# P10_HDMI_Framer.net
KiCad netlist of a schematic drawn in Altium Designer
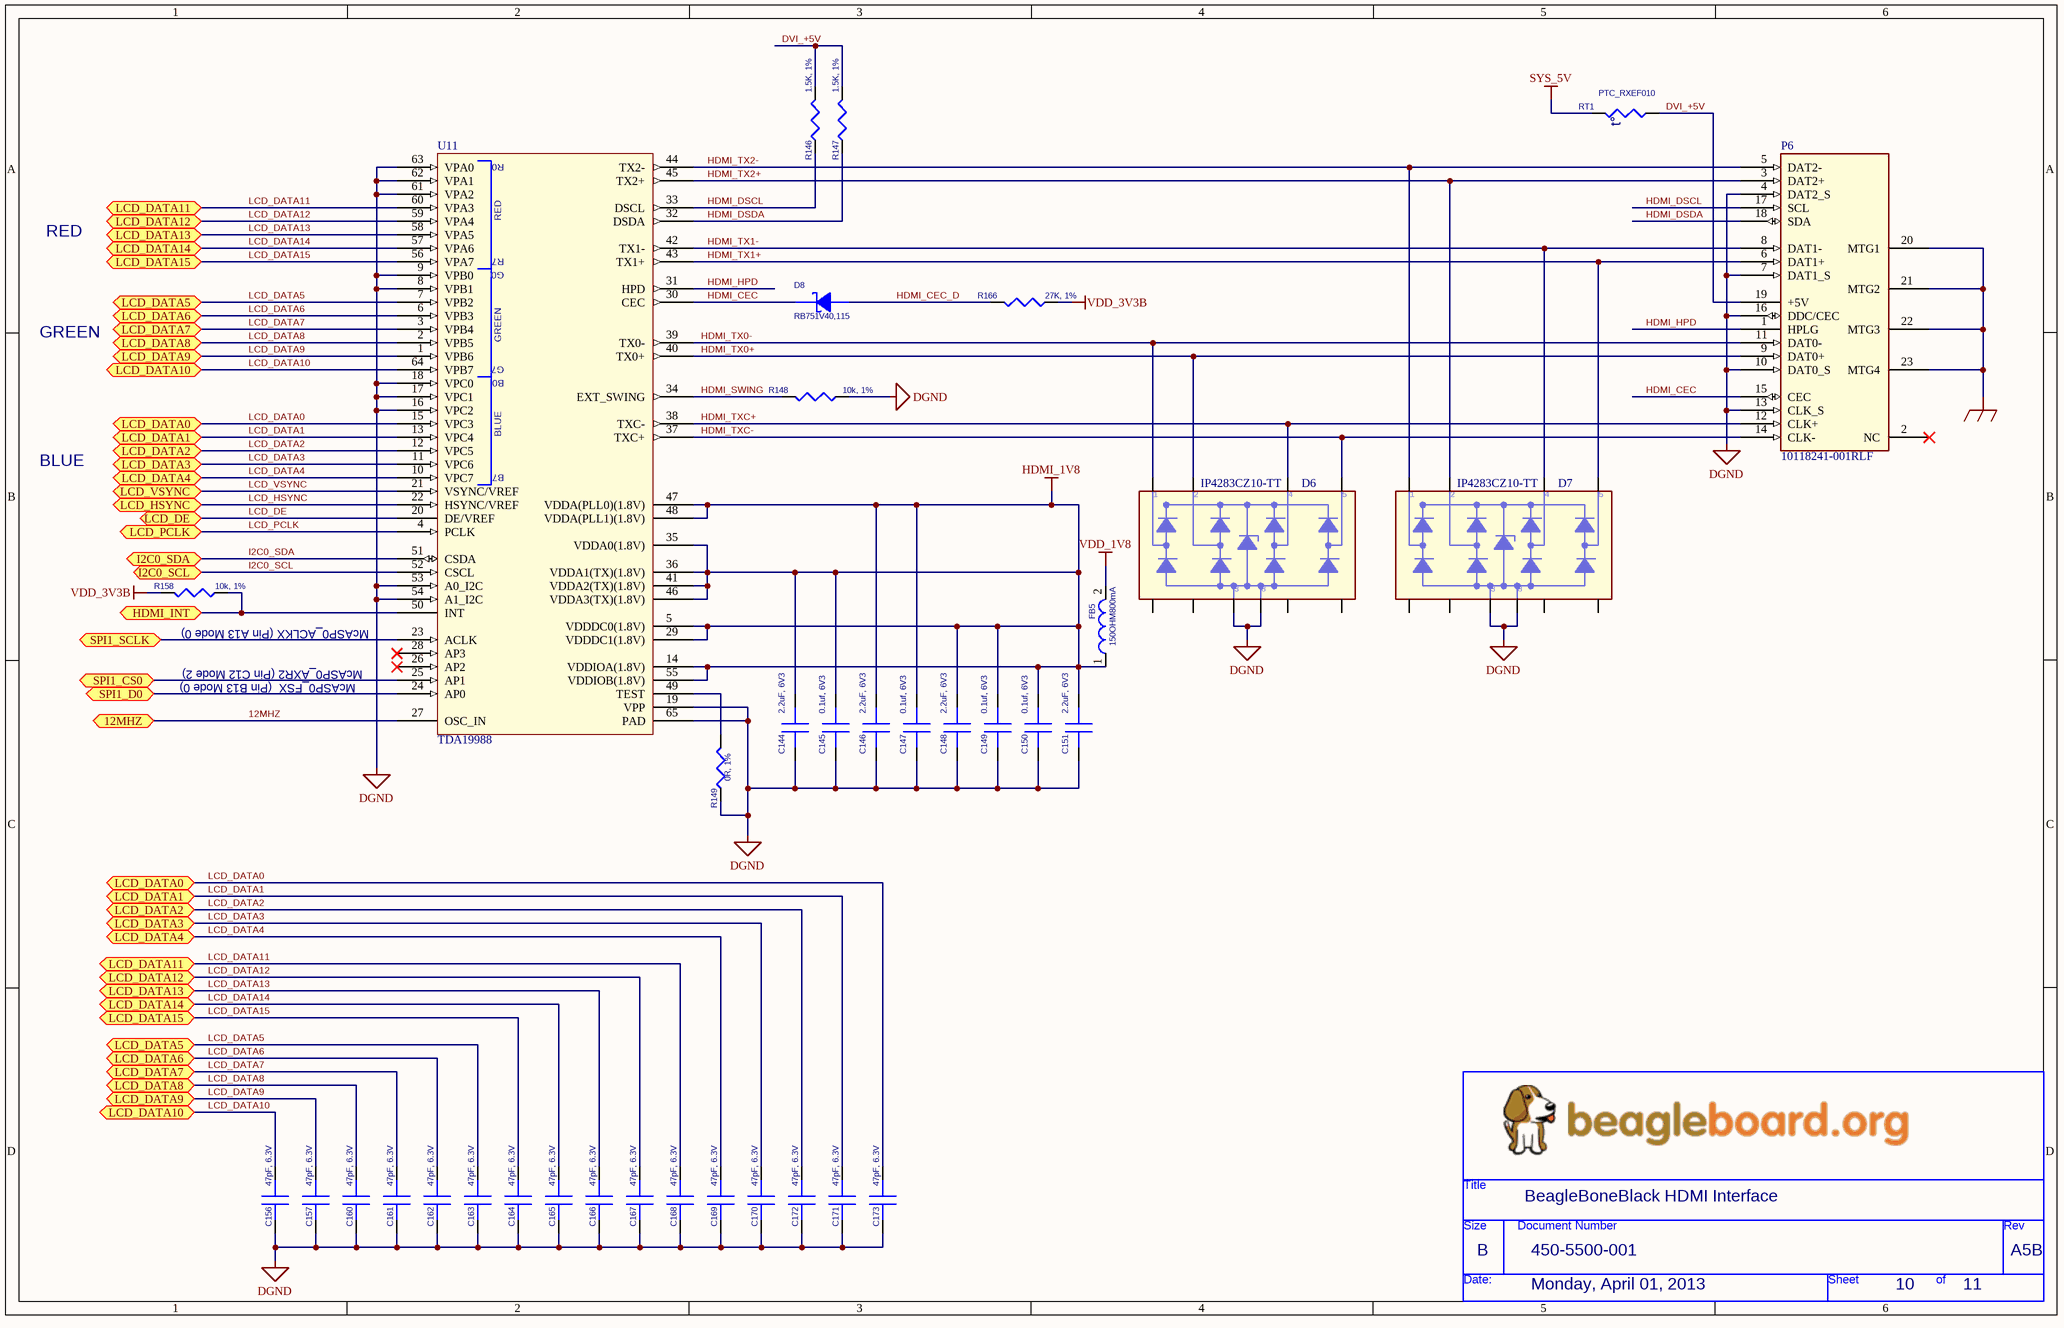
[diagram p0: P10_HDMI Framer.SchDoc]

(export (version "E")
  (design (tool "Eeschema 10.0.6"))
  (components
    (comp (ref "C144")
      (value "2.2uF, 6V3")
      (footprint "402")
      (description "CAP CER 2.2UF 6.3V 10% X5R 0402")
      (fields
        (field (name "MANUFACTURER") "TDK Corporation")
        (field (name "MANUFACTURER PART NUMBER") "C1005X5R0J225K050BC")
      )
      (libsource (lib "BEAGLEBONEBLACK_REV A5B") (part "CAP SMD"))
    )
    (comp (ref "C145")
      (value "0.1uf, 6V3")
      (footprint "402")
      (description "CAP CER 0.1UF 6.3V 10% X5R 0402")
      (fields
        (field (name "MANUFACTURER") "TDK Corporation")
        (field (name "MANUFACTURER PART NUMBER") "C1005X5R0J104K050BA")
      )
      (libsource (lib "BEAGLEBONEBLACK_REV A5B") (part "CAP SMD"))
    )
    (comp (ref "C146")
      (value "2.2uF, 6V3")
      (footprint "402")
      (description "CAP CER 2.2UF 6.3V 10% X5R 0402")
      (fields
        (field (name "MANUFACTURER") "TDK Corporation")
        (field (name "MANUFACTURER PART NUMBER") "C1005X5R0J225K050BC")
      )
      (libsource (lib "BEAGLEBONEBLACK_REV A5B") (part "CAP SMD"))
    )
    (comp (ref "C147")
      (value "0.1uf, 6V3")
      (footprint "402")
      (description "CAP CER 0.1UF 6.3V 10% X5R 0402")
      (fields
        (field (name "MANUFACTURER") "TDK Corporation")
        (field (name "MANUFACTURER PART NUMBER") "C1005X5R0J104K050BA")
      )
      (libsource (lib "BEAGLEBONEBLACK_REV A5B") (part "CAP SMD"))
    )
    (comp (ref "C148")
      (value "2.2uF, 6V3")
      (footprint "402")
      (description "CAP CER 2.2UF 6.3V 10% X5R 0402")
      (fields
        (field (name "MANUFACTURER") "TDK Corporation")
        (field (name "MANUFACTURER PART NUMBER") "C1005X5R0J225K050BC")
      )
      (libsource (lib "BEAGLEBONEBLACK_REV A5B") (part "CAP SMD"))
    )
    (comp (ref "C149")
      (value "0.1uf, 6V3")
      (footprint "402")
      (description "CAP CER 0.1UF 6.3V 10% X5R 0402")
      (fields
        (field (name "MANUFACTURER") "TDK Corporation")
        (field (name "MANUFACTURER PART NUMBER") "C1005X5R0J104K050BA")
      )
      (libsource (lib "BEAGLEBONEBLACK_REV A5B") (part "CAP SMD"))
    )
    (comp (ref "C150")
      (value "0.1uf, 6V3")
      (footprint "402")
      (description "CAP CER 0.1UF 6.3V 10% X5R 0402")
      (fields
        (field (name "MANUFACTURER") "TDK Corporation")
        (field (name "MANUFACTURER PART NUMBER") "C1005X5R0J104K050BA")
      )
      (libsource (lib "BEAGLEBONEBLACK_REV A5B") (part "CAP SMD"))
    )
    (comp (ref "C151")
      (value "2.2uF, 6V3")
      (footprint "402")
      (description "CAP CER 2.2UF 6.3V 10% X5R 0402")
      (fields
        (field (name "MANUFACTURER") "TDK Corporation")
        (field (name "MANUFACTURER PART NUMBER") "C1005X5R0J225K050BC")
      )
      (libsource (lib "BEAGLEBONEBLACK_REV A5B") (part "CAP SMD"))
    )
    (comp (ref "C156")
      (value "47pF, 6.3V")
      (footprint "402")
      (description "CAP CER 47PF 50V 5% NP0 0402")
      (fields
        (field (name "MANUFACTURER") "TDK Corporation")
        (field (name "MANUFACTURER PART NUMBER") "C1005C0G1H470J050BA")
      )
      (libsource (lib "BEAGLEBONEBLACK_REV A5B") (part "CAP SMD"))
    )
    (comp (ref "C157")
      (value "47pF, 6.3V")
      (footprint "402")
      (description "CAP CER 47PF 50V 5% NP0 0402")
      (fields
        (field (name "MANUFACTURER") "TDK Corporation")
        (field (name "MANUFACTURER PART NUMBER") "C1005C0G1H470J050BA")
      )
      (libsource (lib "BEAGLEBONEBLACK_REV A5B") (part "CAP SMD"))
    )
    (comp (ref "C160")
      (value "47pF, 6.3V")
      (footprint "402")
      (description "CAP CER 47PF 50V 5% NP0 0402")
      (fields
        (field (name "MANUFACTURER") "TDK Corporation")
        (field (name "MANUFACTURER PART NUMBER") "C1005C0G1H470J050BA")
      )
      (libsource (lib "BEAGLEBONEBLACK_REV A5B") (part "CAP SMD"))
    )
    (comp (ref "C161")
      (value "47pF, 6.3V")
      (footprint "402")
      (description "CAP CER 47PF 50V 5% NP0 0402")
      (fields
        (field (name "MANUFACTURER") "TDK Corporation")
        (field (name "MANUFACTURER PART NUMBER") "C1005C0G1H470J050BA")
      )
      (libsource (lib "BEAGLEBONEBLACK_REV A5B") (part "CAP SMD"))
    )
    (comp (ref "C162")
      (value "47pF, 6.3V")
      (footprint "402")
      (description "CAP CER 47PF 50V 5% NP0 0402")
      (fields
        (field (name "MANUFACTURER") "TDK Corporation")
        (field (name "MANUFACTURER PART NUMBER") "C1005C0G1H470J050BA")
      )
      (libsource (lib "BEAGLEBONEBLACK_REV A5B") (part "CAP SMD"))
    )
    (comp (ref "C163")
      (value "47pF, 6.3V")
      (footprint "402")
      (description "CAP CER 47PF 50V 5% NP0 0402")
      (fields
        (field (name "MANUFACTURER") "TDK Corporation")
        (field (name "MANUFACTURER PART NUMBER") "C1005C0G1H470J050BA")
      )
      (libsource (lib "BEAGLEBONEBLACK_REV A5B") (part "CAP SMD"))
    )
    (comp (ref "C164")
      (value "47pF, 6.3V")
      (footprint "402")
      (description "CAP CER 47PF 50V 5% NP0 0402")
      (fields
        (field (name "MANUFACTURER") "TDK Corporation")
        (field (name "MANUFACTURER PART NUMBER") "C1005C0G1H470J050BA")
      )
      (libsource (lib "BEAGLEBONEBLACK_REV A5B") (part "CAP SMD"))
    )
    (comp (ref "C165")
      (value "47pF, 6.3V")
      (footprint "402")
      (description "CAP CER 47PF 50V 5% NP0 0402")
      (fields
        (field (name "MANUFACTURER") "TDK Corporation")
        (field (name "MANUFACTURER PART NUMBER") "C1005C0G1H470J050BA")
      )
      (libsource (lib "BEAGLEBONEBLACK_REV A5B") (part "CAP SMD"))
    )
    (comp (ref "C166")
      (value "47pF, 6.3V")
      (footprint "402")
      (description "CAP CER 47PF 50V 5% NP0 0402")
      (fields
        (field (name "MANUFACTURER") "TDK Corporation")
        (field (name "MANUFACTURER PART NUMBER") "C1005C0G1H470J050BA")
      )
      (libsource (lib "BEAGLEBONEBLACK_REV A5B") (part "CAP SMD"))
    )
    (comp (ref "C167")
      (value "47pF, 6.3V")
      (footprint "402")
      (description "CAP CER 47PF 50V 5% NP0 0402")
      (fields
        (field (name "MANUFACTURER") "TDK Corporation")
        (field (name "MANUFACTURER PART NUMBER") "C1005C0G1H470J050BA")
      )
      (libsource (lib "BEAGLEBONEBLACK_REV A5B") (part "CAP SMD"))
    )
    (comp (ref "C168")
      (value "47pF, 6.3V")
      (footprint "402")
      (description "CAP CER 47PF 50V 5% NP0 0402")
      (fields
        (field (name "MANUFACTURER") "TDK Corporation")
        (field (name "MANUFACTURER PART NUMBER") "C1005C0G1H470J050BA")
      )
      (libsource (lib "BEAGLEBONEBLACK_REV A5B") (part "CAP SMD"))
    )
    (comp (ref "C169")
      (value "47pF, 6.3V")
      (footprint "402")
      (description "CAP CER 47PF 50V 5% NP0 0402")
      (fields
        (field (name "MANUFACTURER") "TDK Corporation")
        (field (name "MANUFACTURER PART NUMBER") "C1005C0G1H470J050BA")
      )
      (libsource (lib "BEAGLEBONEBLACK_REV A5B") (part "CAP SMD"))
    )
    (comp (ref "C170")
      (value "47pF, 6.3V")
      (footprint "402")
      (description "CAP CER 47PF 50V 5% NP0 0402")
      (fields
        (field (name "MANUFACTURER") "TDK Corporation")
        (field (name "MANUFACTURER PART NUMBER") "C1005C0G1H470J050BA")
      )
      (libsource (lib "BEAGLEBONEBLACK_REV A5B") (part "CAP SMD"))
    )
    (comp (ref "C171")
      (value "47pF, 6.3V")
      (footprint "402")
      (description "CAP CER 47PF 50V 5% NP0 0402")
      (fields
        (field (name "MANUFACTURER") "TDK Corporation")
        (field (name "MANUFACTURER PART NUMBER") "C1005C0G1H470J050BA")
      )
      (libsource (lib "BEAGLEBONEBLACK_REV A5B") (part "CAP SMD"))
    )
    (comp (ref "C172")
      (value "47pF, 6.3V")
      (footprint "402")
      (description "CAP CER 47PF 50V 5% NP0 0402")
      (fields
        (field (name "MANUFACTURER") "TDK Corporation")
        (field (name "MANUFACTURER PART NUMBER") "C1005C0G1H470J050BA")
      )
      (libsource (lib "BEAGLEBONEBLACK_REV A5B") (part "CAP SMD"))
    )
    (comp (ref "C173")
      (value "47pF, 6.3V")
      (footprint "402")
      (description "CAP CER 47PF 50V 5% NP0 0402")
      (fields
        (field (name "MANUFACTURER") "TDK Corporation")
        (field (name "MANUFACTURER PART NUMBER") "C1005C0G1H470J050BA")
      )
      (libsource (lib "BEAGLEBONEBLACK_REV A5B") (part "CAP SMD"))
    )
    (comp (ref "D6")
      (value "IP4283CZ10-TT")
      (footprint "TSSOP10")
      (description "DIODE ESD PROT HDMI 10TSSOP")
      (fields
        (field (name "MANUFACTURER") "NXP Semiconductors")
        (field (name "MANUFACTURER PART NUMBER") "IP4283CZ10-TT,118")
      )
      (libsource (lib "BEAGLEBONEBLACK_REV A5B") (part "32CTQ030/TO_1"))
    )
    (comp (ref "D7")
      (value "IP4283CZ10-TT")
      (footprint "TSSOP10")
      (description "DIODE ESD PROT HDMI 10TSSOP")
      (fields
        (field (name "MANUFACTURER") "NXP Semiconductors")
        (field (name "MANUFACTURER PART NUMBER") "IP4283CZ10-TT,118")
      )
      (libsource (lib "BEAGLEBONEBLACK_REV A5B") (part "32CTQ030/TO_1"))
    )
    (comp (ref "D8")
      (value "RB751V40,115")
      (footprint "SOD323")
      (description "DIODE SCHOTTKY 40V 120MA SOD323")
      (fields (field (name "MANUFACTURER") "NXP Semiconductors"))
      (libsource (lib "BEAGLEBONEBLACK_REV A5B") (part "Zener"))
    )
    (comp (ref "FB5")
      (value "150OHM800mA")
      (footprint "SM-7351-IND-0805")
      (description "FERRITE 800MA 150 OHM 0805 SMD")
      (fields
        (field (name "MANUFACTURER") "Laird-Signal Integrity Products")
        (field (name "MANUFACTURER PART NUMBER") "LI0805H151R-10")
      )
      (libsource (lib "BEAGLEBONEBLACK_REV A5B") (part "IND"))
    )
    (comp (ref "P6")
      (value "10118241-001RLF")
      (footprint "CONN19_HDMI")
      (description "CONN HDMI RECPT 19POS SMT R/A")
      (fields (field (name "MANUFACTURER") "FCI"))
      (libsource (lib "BEAGLEBONEBLACK_REV A5B") (part "Micro HDMI"))
    )
    (comp (ref "R146")
      (value "1.5K, 1%")
      (footprint "402")
      (description "RES 1.50K OHM 1/16W 1% 0402 SMD")
      (fields
        (field (name "MANUFACTURER") "Yageo")
        (field (name "MANUFACTURER PART NUMBER") "RC0402FR-071K5L")
      )
      (libsource (lib "BEAGLEBONEBLACK_REV A5B") (part "RES SMD"))
    )
    (comp (ref "R147")
      (value "1.5K, 1%")
      (footprint "402")
      (description "RES 1.50K OHM 1/16W 1% 0402 SMD")
      (fields
        (field (name "MANUFACTURER") "Yageo")
        (field (name "MANUFACTURER PART NUMBER") "RC0402FR-071K5L")
      )
      (libsource (lib "BEAGLEBONEBLACK_REV A5B") (part "RES SMD"))
    )
    (comp (ref "R148")
      (value "10k, 1%")
      (footprint "402")
      (description "RES 10K OHM 1/16W 5% 0402 SMD")
      (fields
        (field (name "MANUFACTURER") "Rohm Semiconductor")
        (field (name "MANUFACTURER PART NUMBER") "MCR01MZPJ103")
      )
      (libsource (lib "BEAGLEBONEBLACK_REV A5B") (part "RES SMD"))
    )
    (comp (ref "R149")
      (value "0R, 1%")
      (footprint "402")
      (description "RES 0.0 OHM 1/16W 0402 SMD")
      (fields
        (field (name "MANUFACTURER") "Yageo")
        (field (name "MANUFACTURER PART NUMBER") "RC0402JR-070RL")
      )
      (libsource (lib "BEAGLEBONEBLACK_REV A5B") (part "RES SMD"))
    )
    (comp (ref "R158")
      (value "10k, 1%")
      (footprint "402")
      (description "RES 10K OHM 1/16W 5% 0402 SMD")
      (fields
        (field (name "MANUFACTURER") "Rohm Semiconductor")
        (field (name "MANUFACTURER PART NUMBER") "MCR01MZPJ103")
      )
      (libsource (lib "BEAGLEBONEBLACK_REV A5B") (part "RES SMD"))
    )
    (comp (ref "R166")
      (value "27K, 1%")
      (footprint "402")
      (description "RES 27.0K OHM 1/16W 1% 0402 SMD")
      (fields
        (field (name "MANUFACTURER") "Yageo")
        (field (name "MANUFACTURER PART NUMBER") "RC0402FR-0727KL")
      )
      (libsource (lib "BEAGLEBONEBLACK_REV A5B") (part "RES SMD"))
    )
    (comp (ref "RT1")
      (value "PTC_RXEF010")
      (footprint "POLYSW200-5638-310")
      (description "POLYSWITCH PTC RESET 0.1A")
      (fields
        (field (name "MANUFACTURER") "TE Connectivity")
        (field (name "MANUFACTURER PART NUMBER") "RXEF010")
      )
      (libsource (lib "BEAGLEBONEBLACK_REV A5B") (part "PTC"))
    )
    (comp (ref "U11")
      (value "TDA19988")
      (footprint "QFN64S9X9P5")
      (description "IC HDMI TRANSMITTER 64-HVQFN")
      (fields
        (field (name "MANUFACTURER") "NXP Semiconductors")
        (field (name "MANUFACTURER PART NUMBER") "TDA19988AHN/C1,551")
      )
      (libsource (lib "BEAGLEBONEBLACK_REV A5B") (part "TDA19988"))
    )
  )
  (nets
    (net (code "1") (name "/12MHZ") (class "Default")
      (node (ref "U11") (pin "27") (pinfunction "OSC_IN_27") (pintype "passive"))
    )
    (net (code "2") (name "/DVI_+5V") (class "Default")
      (node (ref "P6") (pin "19") (pinfunction "+5V_19") (pintype "power_in"))
      (node (ref "R146") (pin "1") (pinfunction "P1_1") (pintype "passive"))
      (node (ref "R147") (pin "1") (pinfunction "P1_1") (pintype "passive"))
      (node (ref "RT1") (pin "2") (pinfunction "P2_2") (pintype "passive"))
    )
    (net (code "3") (name "/HDMI_CEC") (class "Default")
      (node (ref "D8") (pin "1") (pinfunction "C_1") (pintype "passive"))
      (node (ref "P6") (pin "15") (pinfunction "CEC_15") (pintype "bidirectional"))
      (node (ref "U11") (pin "30") (pinfunction "CEC_30") (pintype "output"))
    )
    (net (code "4") (name "/HDMI_CEC_D") (class "Default")
      (node (ref "D8") (pin "2") (pinfunction "A_2") (pintype "passive"))
      (node (ref "R166") (pin "1") (pinfunction "P1_1") (pintype "passive"))
    )
    (net (code "5") (name "/HDMI_DSCL") (class "Default")
      (node (ref "P6") (pin "17") (pinfunction "SCL_17") (pintype "input"))
      (node (ref "R146") (pin "2") (pinfunction "P2_2") (pintype "passive"))
      (node (ref "U11") (pin "33") (pinfunction "DSCL_33") (pintype "output"))
    )
    (net (code "6") (name "/HDMI_DSDA") (class "Default")
      (node (ref "P6") (pin "18") (pinfunction "SDA_18") (pintype "bidirectional"))
      (node (ref "R147") (pin "2") (pinfunction "P2_2") (pintype "passive"))
      (node (ref "U11") (pin "32") (pinfunction "DSDA_32") (pintype "output"))
    )
    (net (code "7") (name "/HDMI_HPD") (class "Default")
      (node (ref "P6") (pin "1") (pinfunction "HPLG_1") (pintype "passive"))
      (node (ref "U11") (pin "31") (pinfunction "HPD_31") (pintype "output"))
    )
    (net (code "8") (name "/HDMI_INT") (class "Default")
      (node (ref "R158") (pin "2") (pinfunction "P2_2") (pintype "passive"))
      (node (ref "U11") (pin "50") (pinfunction "INT_50") (pintype "open_collector"))
    )
    (net (code "9") (name "/HDMI_SWING") (class "Default")
      (node (ref "R148") (pin "1") (pinfunction "P1_1") (pintype "passive"))
      (node (ref "U11") (pin "34") (pinfunction "EXT_SWING_34") (pintype "output"))
    )
    (net (code "10") (name "/HDMI_TX0+") (class "Default")
      (node (ref "D6") (pin "2") (pinfunction "2_2") (pintype "passive"))
      (node (ref "P6") (pin "9") (pinfunction "DAT0+_9") (pintype "input"))
      (node (ref "U11") (pin "40") (pinfunction "TX0+_40") (pintype "output"))
    )
    (net (code "11") (name "/HDMI_TX0-") (class "Default")
      (node (ref "D6") (pin "1") (pinfunction "1_1") (pintype "passive"))
      (node (ref "P6") (pin "11") (pinfunction "DAT0-_11") (pintype "input"))
      (node (ref "U11") (pin "39") (pinfunction "TX0-_39") (pintype "output"))
    )
    (net (code "12") (name "/HDMI_TX1+") (class "Default")
      (node (ref "D7") (pin "5") (pinfunction "5_5") (pintype "passive"))
      (node (ref "P6") (pin "6") (pinfunction "DAT1+_6") (pintype "input"))
      (node (ref "U11") (pin "43") (pinfunction "TX1+_43") (pintype "output"))
    )
    (net (code "13") (name "/HDMI_TX1-") (class "Default")
      (node (ref "D7") (pin "4") (pinfunction "4_4") (pintype "passive"))
      (node (ref "P6") (pin "8") (pinfunction "DAT1-_8") (pintype "input"))
      (node (ref "U11") (pin "42") (pinfunction "TX1-_42") (pintype "output"))
    )
    (net (code "14") (name "/HDMI_TX2+") (class "Default")
      (node (ref "D7") (pin "2") (pinfunction "2_2") (pintype "passive"))
      (node (ref "P6") (pin "3") (pinfunction "DAT2+_3") (pintype "input"))
      (node (ref "U11") (pin "45") (pinfunction "TX2+_45") (pintype "output"))
    )
    (net (code "15") (name "/HDMI_TX2-") (class "Default")
      (node (ref "D7") (pin "1") (pinfunction "1_1") (pintype "passive"))
      (node (ref "P6") (pin "5") (pinfunction "DAT2-_5") (pintype "input"))
      (node (ref "U11") (pin "44") (pinfunction "TX2-_44") (pintype "output"))
    )
    (net (code "16") (name "/HDMI_TXC+") (class "Default")
      (node (ref "D6") (pin "4") (pinfunction "4_4") (pintype "passive"))
      (node (ref "P6") (pin "12") (pinfunction "CLK+_12") (pintype "input"))
      (node (ref "U11") (pin "38") (pinfunction "TXC-_38") (pintype "output"))
    )
    (net (code "17") (name "/HDMI_TXC-") (class "Default")
      (node (ref "D6") (pin "5") (pinfunction "5_5") (pintype "passive"))
      (node (ref "P6") (pin "14") (pinfunction "CLK-_14") (pintype "input"))
      (node (ref "U11") (pin "37") (pinfunction "TXC+_37") (pintype "output"))
    )
    (net (code "18") (name "/I2C0_SCL") (class "Default")
      (node (ref "U11") (pin "52") (pinfunction "CSCL_52") (pintype "input"))
    )
    (net (code "19") (name "/I2C0_SDA") (class "Default")
      (node (ref "U11") (pin "51") (pinfunction "CSDA_51") (pintype "bidirectional"))
    )
    (net (code "20") (name "/LCD_DATA0") (class "Default")
      (node (ref "C173") (pin "1") (pinfunction "1_1") (pintype "passive"))
      (node (ref "U11") (pin "15") (pinfunction "VPC3_15") (pintype "input"))
    )
    (net (code "21") (name "/LCD_DATA1") (class "Default")
      (node (ref "C171") (pin "1") (pinfunction "1_1") (pintype "passive"))
      (node (ref "U11") (pin "13") (pinfunction "VPC4_13") (pintype "input"))
    )
    (net (code "22") (name "/LCD_DATA2") (class "Default")
      (node (ref "C172") (pin "1") (pinfunction "1_1") (pintype "passive"))
      (node (ref "U11") (pin "12") (pinfunction "VPC5_12") (pintype "input"))
    )
    (net (code "23") (name "/LCD_DATA3") (class "Default")
      (node (ref "C170") (pin "1") (pinfunction "1_1") (pintype "passive"))
      (node (ref "U11") (pin "11") (pinfunction "VPC6_11") (pintype "input"))
    )
    (net (code "24") (name "/LCD_DATA4") (class "Default")
      (node (ref "C169") (pin "1") (pinfunction "1_1") (pintype "passive"))
      (node (ref "U11") (pin "10") (pinfunction "VPC7_10") (pintype "input"))
    )
    (net (code "25") (name "/LCD_DATA5") (class "Default")
      (node (ref "C163") (pin "1") (pinfunction "1_1") (pintype "passive"))
      (node (ref "U11") (pin "7") (pinfunction "VPB2_7") (pintype "input"))
    )
    (net (code "26") (name "/LCD_DATA6") (class "Default")
      (node (ref "C162") (pin "1") (pinfunction "1_1") (pintype "passive"))
      (node (ref "U11") (pin "6") (pinfunction "VPB3_6") (pintype "input"))
    )
    (net (code "27") (name "/LCD_DATA7") (class "Default")
      (node (ref "C161") (pin "1") (pinfunction "1_1") (pintype "passive"))
      (node (ref "U11") (pin "3") (pinfunction "VPB4_3") (pintype "input"))
    )
    (net (code "28") (name "/LCD_DATA8") (class "Default")
      (node (ref "C160") (pin "1") (pinfunction "1_1") (pintype "passive"))
      (node (ref "U11") (pin "2") (pinfunction "VPB5_2") (pintype "input"))
    )
    (net (code "29") (name "/LCD_DATA9") (class "Default")
      (node (ref "C157") (pin "1") (pinfunction "1_1") (pintype "passive"))
      (node (ref "U11") (pin "1") (pinfunction "VPB6_1") (pintype "input"))
    )
    (net (code "30") (name "/LCD_DATA10") (class "Default")
      (node (ref "C156") (pin "1") (pinfunction "1_1") (pintype "passive"))
      (node (ref "U11") (pin "64") (pinfunction "VPB7_64") (pintype "input"))
    )
    (net (code "31") (name "/LCD_DATA11") (class "Default")
      (node (ref "C168") (pin "1") (pinfunction "1_1") (pintype "passive"))
      (node (ref "U11") (pin "60") (pinfunction "VPA3_60") (pintype "input"))
    )
    (net (code "32") (name "/LCD_DATA12") (class "Default")
      (node (ref "C167") (pin "1") (pinfunction "1_1") (pintype "passive"))
      (node (ref "U11") (pin "59") (pinfunction "VPA4_59") (pintype "input"))
    )
    (net (code "33") (name "/LCD_DATA13") (class "Default")
      (node (ref "C166") (pin "1") (pinfunction "1_1") (pintype "passive"))
      (node (ref "U11") (pin "58") (pinfunction "VPA5_58") (pintype "input"))
    )
    (net (code "34") (name "/LCD_DATA14") (class "Default")
      (node (ref "C165") (pin "1") (pinfunction "1_1") (pintype "passive"))
      (node (ref "U11") (pin "57") (pinfunction "VPA6_57") (pintype "input"))
    )
    (net (code "35") (name "/LCD_DATA15") (class "Default")
      (node (ref "C164") (pin "1") (pinfunction "1_1") (pintype "passive"))
      (node (ref "U11") (pin "56") (pinfunction "VPA7_56") (pintype "input"))
    )
    (net (code "36") (name "/LCD_DE") (class "Default")
      (node (ref "U11") (pin "20") (pinfunction "DE/VREF_20") (pintype "passive"))
    )
    (net (code "37") (name "/LCD_HSYNC") (class "Default")
      (node (ref "U11") (pin "22") (pinfunction "HSYNC/VREF_22") (pintype "input"))
    )
    (net (code "38") (name "/LCD_PCLK") (class "Default")
      (node (ref "U11") (pin "4") (pinfunction "PCLK_4") (pintype "input"))
    )
    (net (code "39") (name "/LCD_VSYNC") (class "Default")
      (node (ref "U11") (pin "21") (pinfunction "VSYNC/VREF_21") (pintype "input"))
    )
    (net (code "40") (name "/SPI1_CS0") (class "Default")
      (node (ref "U11") (pin "25") (pinfunction "AP1_25") (pintype "input"))
    )
    (net (code "41") (name "/SPI1_D0") (class "Default")
      (node (ref "U11") (pin "24") (pinfunction "AP0_24") (pintype "input"))
    )
    (net (code "42") (name "/SPI1_SCLK") (class "Default")
      (node (ref "U11") (pin "23") (pinfunction "ACLK_23") (pintype "input"))
    )
    (net (code "43") (name "DGND") (class "Default")
      (node (ref "C144") (pin "2") (pinfunction "2_2") (pintype "passive"))
      (node (ref "C145") (pin "2") (pinfunction "2_2") (pintype "passive"))
      (node (ref "C146") (pin "2") (pinfunction "2_2") (pintype "passive"))
      (node (ref "C147") (pin "2") (pinfunction "2_2") (pintype "passive"))
      (node (ref "C148") (pin "2") (pinfunction "2_2") (pintype "passive"))
      (node (ref "C149") (pin "2") (pinfunction "2_2") (pintype "passive"))
      (node (ref "C150") (pin "2") (pinfunction "2_2") (pintype "passive"))
      (node (ref "C151") (pin "2") (pinfunction "2_2") (pintype "passive"))
      (node (ref "C156") (pin "2") (pinfunction "2_2") (pintype "passive"))
      (node (ref "C157") (pin "2") (pinfunction "2_2") (pintype "passive"))
      (node (ref "C160") (pin "2") (pinfunction "2_2") (pintype "passive"))
      (node (ref "C161") (pin "2") (pinfunction "2_2") (pintype "passive"))
      (node (ref "C162") (pin "2") (pinfunction "2_2") (pintype "passive"))
      (node (ref "C163") (pin "2") (pinfunction "2_2") (pintype "passive"))
      (node (ref "C164") (pin "2") (pinfunction "2_2") (pintype "passive"))
      (node (ref "C165") (pin "2") (pinfunction "2_2") (pintype "passive"))
      (node (ref "C166") (pin "2") (pinfunction "2_2") (pintype "passive"))
      (node (ref "C167") (pin "2") (pinfunction "2_2") (pintype "passive"))
      (node (ref "C168") (pin "2") (pinfunction "2_2") (pintype "passive"))
      (node (ref "C169") (pin "2") (pinfunction "2_2") (pintype "passive"))
      (node (ref "C170") (pin "2") (pinfunction "2_2") (pintype "passive"))
      (node (ref "C171") (pin "2") (pinfunction "2_2") (pintype "passive"))
      (node (ref "C172") (pin "2") (pinfunction "2_2") (pintype "passive"))
      (node (ref "C173") (pin "2") (pinfunction "2_2") (pintype "passive"))
      (node (ref "D6") (pin "3") (pinfunction "3_3") (pintype "passive"))
      (node (ref "D6") (pin "8") (pinfunction "8_8") (pintype "passive"))
      (node (ref "D7") (pin "3") (pinfunction "3_3") (pintype "passive"))
      (node (ref "D7") (pin "8") (pinfunction "8_8") (pintype "passive"))
      (node (ref "P6") (pin "10") (pinfunction "DAT0_S_10") (pintype "input"))
      (node (ref "P6") (pin "13") (pinfunction "CLK_S_13") (pintype "input"))
      (node (ref "P6") (pin "16") (pinfunction "DDC/CEC_16") (pintype "bidirectional"))
      (node (ref "P6") (pin "4") (pinfunction "DAT2_S_4") (pintype "input"))
      (node (ref "P6") (pin "7") (pinfunction "DAT1_S_7") (pintype "input"))
      (node (ref "R148") (pin "2") (pinfunction "P2_2") (pintype "passive"))
      (node (ref "R149") (pin "2") (pinfunction "P2_2") (pintype "passive"))
      (node (ref "U11") (pin "16") (pinfunction "VPC2_16") (pintype "input"))
      (node (ref "U11") (pin "17") (pinfunction "VPC1_17") (pintype "input"))
      (node (ref "U11") (pin "18") (pinfunction "VPC0_18") (pintype "input"))
      (node (ref "U11") (pin "19") (pinfunction "VPP_19") (pintype "power_in"))
      (node (ref "U11") (pin "53") (pinfunction "A0_I2C_53") (pintype "input"))
      (node (ref "U11") (pin "54") (pinfunction "A1_I2C_54") (pintype "input"))
      (node (ref "U11") (pin "61") (pinfunction "VPA2_61") (pintype "input"))
      (node (ref "U11") (pin "62") (pinfunction "VPA1_62") (pintype "input"))
      (node (ref "U11") (pin "63") (pinfunction "VPA0_63") (pintype "input"))
      (node (ref "U11") (pin "65") (pinfunction "PAD_65") (pintype "power_in"))
      (node (ref "U11") (pin "8") (pinfunction "VPB1_8") (pintype "input"))
      (node (ref "U11") (pin "9") (pinfunction "VPB0_9") (pintype "input"))
    )
    (net (code "44") (name "GND_EARTH") (class "Default")
      (node (ref "P6") (pin "20") (pinfunction "MTG1_20") (pintype "passive"))
      (node (ref "P6") (pin "21") (pinfunction "MTG2_21") (pintype "passive"))
      (node (ref "P6") (pin "22") (pinfunction "MTG3_22") (pintype "passive"))
      (node (ref "P6") (pin "23") (pinfunction "MTG4_23") (pintype "passive"))
    )
    (net (code "45") (name "HDMI_1V8") (class "Default")
      (node (ref "C144") (pin "1") (pinfunction "1_1") (pintype "passive"))
      (node (ref "C145") (pin "1") (pinfunction "1_1") (pintype "passive"))
      (node (ref "C146") (pin "1") (pinfunction "1_1") (pintype "passive"))
      (node (ref "C147") (pin "1") (pinfunction "1_1") (pintype "passive"))
      (node (ref "C148") (pin "1") (pinfunction "1_1") (pintype "passive"))
      (node (ref "C149") (pin "1") (pinfunction "1_1") (pintype "passive"))
      (node (ref "C150") (pin "1") (pinfunction "1_1") (pintype "passive"))
      (node (ref "C151") (pin "1") (pinfunction "1_1") (pintype "passive"))
      (node (ref "FB5") (pin "1") (pinfunction "1_1") (pintype "passive"))
      (node (ref "U11") (pin "14") (pinfunction "VDDIOA(1.8V)_14") (pintype "power_in"))
      (node (ref "U11") (pin "29") (pinfunction "VDDDC1(1.8V)_29") (pintype "power_in"))
      (node (ref "U11") (pin "35") (pinfunction "VDDA0(1.8V)_35") (pintype "power_in"))
      (node (ref "U11") (pin "36") (pinfunction "VDDA1(TX)(1.8V)_36") (pintype "power_in"))
      (node (ref "U11") (pin "41") (pinfunction "VDDA2(TX)(1.8V)_41") (pintype "power_in"))
      (node (ref "U11") (pin "46") (pinfunction "VDDA3(TX)(1.8V)_46") (pintype "power_in"))
      (node (ref "U11") (pin "47") (pinfunction "VDDA(PLL0)(1.8V)_47") (pintype "power_in"))
      (node (ref "U11") (pin "48") (pinfunction "VDDA(PLL1)(1.8V)_48") (pintype "power_in"))
      (node (ref "U11") (pin "5") (pinfunction "VDDDC0(1.8V)_5") (pintype "power_in"))
      (node (ref "U11") (pin "55") (pinfunction "VDDIOB(1.8V)_55") (pintype "power_in"))
    )
    (net (code "46") (name "Net-(R149-P1)") (class "Default")
      (node (ref "R149") (pin "1") (pinfunction "P1_1") (pintype "passive"))
      (node (ref "U11") (pin "49") (pinfunction "TEST_49") (pintype "passive"))
    )
    (net (code "47") (name "SYS_5V") (class "Default")
      (node (ref "RT1") (pin "1") (pinfunction "P1_1") (pintype "passive"))
    )
    (net (code "48") (name "VDD_1V8") (class "Default")
      (node (ref "FB5") (pin "2") (pinfunction "2_2") (pintype "passive"))
    )
    (net (code "49") (name "VDD_3V3B") (class "Default")
      (node (ref "R158") (pin "1") (pinfunction "P1_1") (pintype "passive"))
      (node (ref "R166") (pin "2") (pinfunction "P2_2") (pintype "passive"))
    )
    (net (code "50") (name "unconnected-(D6-Pad6)") (class "Default")
      (node (ref "D6") (pin "6") (pinfunction "6_6") (pintype "passive"))
    )
    (net (code "51") (name "unconnected-(D6-Pad7)") (class "Default")
      (node (ref "D6") (pin "7") (pinfunction "7_7") (pintype "passive"))
    )
    (net (code "52") (name "unconnected-(D6-Pad9)") (class "Default")
      (node (ref "D6") (pin "9") (pinfunction "9_9") (pintype "passive"))
    )
    (net (code "53") (name "unconnected-(D6-Pad10)") (class "Default")
      (node (ref "D6") (pin "10") (pinfunction "10_10") (pintype "passive"))
    )
    (net (code "54") (name "unconnected-(D7-Pad6)") (class "Default")
      (node (ref "D7") (pin "6") (pinfunction "6_6") (pintype "passive"))
    )
    (net (code "55") (name "unconnected-(D7-Pad7)") (class "Default")
      (node (ref "D7") (pin "7") (pinfunction "7_7") (pintype "passive"))
    )
    (net (code "56") (name "unconnected-(D7-Pad9)") (class "Default")
      (node (ref "D7") (pin "9") (pinfunction "9_9") (pintype "passive"))
    )
    (net (code "57") (name "unconnected-(D7-Pad10)") (class "Default")
      (node (ref "D7") (pin "10") (pinfunction "10_10") (pintype "passive"))
    )
    (net (code "58") (name "unconnected-(P6-NC-Pad2)") (class "Default")
      (node (ref "P6") (pin "2") (pinfunction "NC_2") (pintype "passive+no_connect"))
    )
    (net (code "59") (name "unconnected-(U11-AP2-Pad26)") (class "Default")
      (node (ref "U11") (pin "26") (pinfunction "AP2_26") (pintype "input+no_connect"))
    )
    (net (code "60") (name "unconnected-(U11-AP3-Pad28)") (class "Default")
      (node (ref "U11") (pin "28") (pinfunction "AP3_28") (pintype "input+no_connect"))
    )
  )
)
